# hf-upconverter.net
KiCad netlist of a schematic drawn in EAGLE
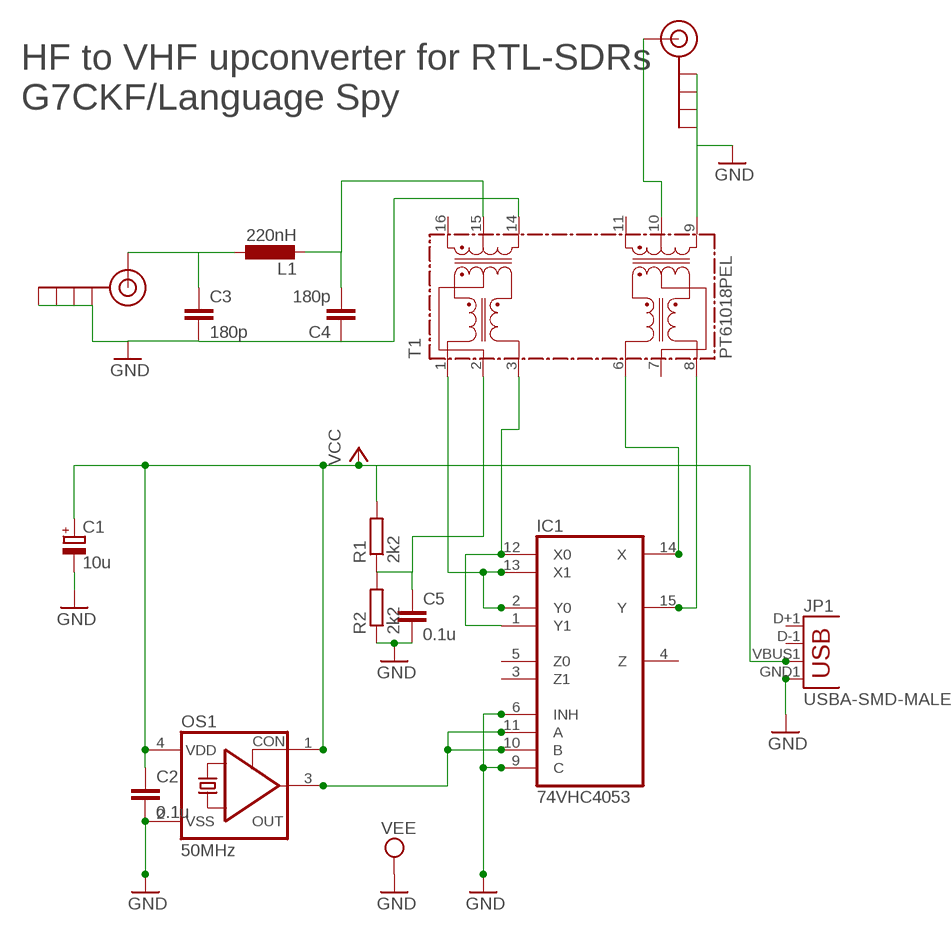
[diagram p0: schematic, sheet 1]

(export (version "E")
  (design (tool "Eeschema 10.0.6"))
  (components
    (comp (ref "C1")
      (value "10u")
      (footprint "eagle-import:PANASONIC_B")
      (libsource (lib "eagle-import") (part "CPOL-EUB"))
    )
    (comp (ref "C2")
      (value "0.1u")
      (footprint "eagle-import:C0805")
      (libsource (lib "eagle-import") (part "C-EUC0805"))
    )
    (comp (ref "C3")
      (value "180p")
      (footprint "eagle-import:C0805")
      (libsource (lib "eagle-import") (part "C-EUC0805"))
    )
    (comp (ref "C4")
      (value "180p")
      (footprint "eagle-import:C0805")
      (libsource (lib "eagle-import") (part "C-EUC0805"))
    )
    (comp (ref "C5")
      (value "0.1u")
      (footprint "eagle-import:C0805")
      (libsource (lib "eagle-import") (part "C-EUC0805"))
    )
    (comp (ref "IC1")
      (value "74VHC4053")
      (footprint "eagle-import:SO16")
      (libsource (lib "eagle-import") (part "4053D"))
    )
    (comp (ref "JP1")
      (value "USBA-SMD-MALE")
      (footprint "eagle-import:USB-A-SMT-MALE")
      (libsource (lib "eagle-import") (part "USBA-SMD-MALE"))
    )
    (comp (ref "L1")
      (value "220nH")
      (footprint "eagle-import:R1206")
      (libsource (lib "eagle-import") (part "L-EU"))
    )
    (comp (ref "OS1")
      (value "50MHz")
      (footprint "eagle-import:7.2X5.2-4-PAD")
      (libsource (lib "eagle-import") (part "OSC-OE-CFPS-32"))
    )
    (comp (ref "R1")
      (value "2k2")
      (footprint "eagle-import:R0805")
      (libsource (lib "eagle-import") (part "R-EU_R0805"))
    )
    (comp (ref "R2")
      (value "2k2")
      (footprint "eagle-import:R0805")
      (libsource (lib "eagle-import") (part "R-EU_R0805"))
    )
    (comp (ref "SMA1")
      (value "ANT")
      (footprint "eagle-import:SMA-EDGE")
      (libsource (lib "eagle-import") (part "SMA_EDGE"))
    )
    (comp (ref "SMA2")
      (value "OUT")
      (footprint "eagle-import:SMA-EDGE")
      (libsource (lib "eagle-import") (part "SMA_EDGE"))
    )
    (comp (ref "T1")
      (value "PT61018PEL")
      (footprint "eagle-import:N5")
      (libsource (lib "eagle-import") (part "TG110-E050N5"))
    )
  )
  (nets
    (net (code "1") (name "GND") (class "Default")
      (node (ref "C1") (pin "-") (pinfunction "-_-") (pintype "passive"))
      (node (ref "C2") (pin "2") (pinfunction "2_2") (pintype "passive"))
      (node (ref "C3") (pin "2") (pinfunction "2_2") (pintype "passive"))
      (node (ref "C4") (pin "1") (pinfunction "1_1") (pintype "passive"))
      (node (ref "C5") (pin "2") (pinfunction "2_2") (pintype "passive"))
      (node (ref "IC1") (pin "6") (pinfunction "INH_6") (pintype "input"))
      (node (ref "IC1") (pin "9") (pinfunction "C_9") (pintype "input"))
      (node (ref "JP1") (pin "GND1") (pinfunction "GND_GND1") (pintype "bidirectional"))
      (node (ref "OS1") (pin "2") (pinfunction "VSS_2") (pintype "power_in"))
      (node (ref "R2") (pin "1") (pinfunction "1_1") (pintype "passive"))
      (node (ref "SMA1") (pin "GND@0") (pinfunction "GND_GND@0") (pintype "bidirectional"))
      (node (ref "SMA1") (pin "GND@1") (pinfunction "GND_GND@1") (pintype "bidirectional"))
      (node (ref "SMA1") (pin "GND@2") (pinfunction "GND_GND@2") (pintype "bidirectional"))
      (node (ref "SMA1") (pin "GND@3") (pinfunction "GND_GND@3") (pintype "bidirectional"))
      (node (ref "SMA2") (pin "GND@0") (pinfunction "GND_GND@0") (pintype "bidirectional"))
      (node (ref "SMA2") (pin "GND@1") (pinfunction "GND_GND@1") (pintype "bidirectional"))
      (node (ref "SMA2") (pin "GND@2") (pinfunction "GND_GND@2") (pintype "bidirectional"))
      (node (ref "SMA2") (pin "GND@3") (pinfunction "GND_GND@3") (pintype "bidirectional"))
      (node (ref "T1") (pin "14") (pinfunction "14_14") (pintype "passive"))
      (node (ref "T1") (pin "9") (pinfunction "9_9") (pintype "passive"))
    )
    (net (code "2") (name "Net-(C4-Pad2)") (class "Default")
      (node (ref "C4") (pin "2") (pinfunction "2_2") (pintype "passive"))
      (node (ref "L1") (pin "2") (pinfunction "2_2") (pintype "passive"))
      (node (ref "T1") (pin "15") (pinfunction "15_15") (pintype "passive"))
    )
    (net (code "3") (name "Net-(C5-Pad1)") (class "Default")
      (node (ref "C5") (pin "1") (pinfunction "1_1") (pintype "passive"))
      (node (ref "R1") (pin "1") (pinfunction "1_1") (pintype "passive"))
      (node (ref "R2") (pin "2") (pinfunction "2_2") (pintype "passive"))
      (node (ref "T1") (pin "2") (pinfunction "2_2") (pintype "passive"))
    )
    (net (code "4") (name "Net-(IC1A-A)") (class "Default")
      (node (ref "IC1") (pin "10") (pinfunction "B_10") (pintype "input"))
      (node (ref "IC1") (pin "11") (pinfunction "A_11") (pintype "input"))
      (node (ref "OS1") (pin "3") (pinfunction "OUT_3") (pintype "output"))
    )
    (net (code "5") (name "Net-(IC1A-X)") (class "Default")
      (node (ref "IC1") (pin "14") (pinfunction "X_14") (pintype "bidirectional"))
      (node (ref "T1") (pin "6") (pinfunction "6_6") (pintype "passive"))
    )
    (net (code "6") (name "Net-(IC1A-X0)") (class "Default")
      (node (ref "IC1") (pin "1") (pinfunction "Y1_1") (pintype "bidirectional"))
      (node (ref "IC1") (pin "12") (pinfunction "X0_12") (pintype "bidirectional"))
      (node (ref "T1") (pin "3") (pinfunction "3_3") (pintype "passive"))
    )
    (net (code "7") (name "Net-(IC1A-X1)") (class "Default")
      (node (ref "IC1") (pin "13") (pinfunction "X1_13") (pintype "bidirectional"))
      (node (ref "IC1") (pin "2") (pinfunction "Y0_2") (pintype "bidirectional"))
      (node (ref "T1") (pin "1") (pinfunction "1_1") (pintype "passive"))
    )
    (net (code "8") (name "Net-(IC1A-Y)") (class "Default")
      (node (ref "IC1") (pin "15") (pinfunction "Y_15") (pintype "bidirectional"))
      (node (ref "T1") (pin "8") (pinfunction "8_8") (pintype "passive"))
    )
    (net (code "9") (name "Net-(SMA1-SIGNAL)") (class "Default")
      (node (ref "C3") (pin "1") (pinfunction "1_1") (pintype "passive"))
      (node (ref "L1") (pin "1") (pinfunction "1_1") (pintype "passive"))
      (node (ref "SMA1") (pin "SIG") (pinfunction "SIGNAL_SIG") (pintype "bidirectional"))
    )
    (net (code "10") (name "Net-(SMA2-SIGNAL)") (class "Default")
      (node (ref "SMA2") (pin "SIG") (pinfunction "SIGNAL_SIG") (pintype "bidirectional"))
      (node (ref "T1") (pin "10") (pinfunction "10_10") (pintype "passive"))
    )
    (net (code "11") (name "VCC") (class "Default")
      (node (ref "C1") (pin "+") (pinfunction "+_+") (pintype "passive"))
      (node (ref "C2") (pin "1") (pinfunction "1_1") (pintype "passive"))
      (node (ref "JP1") (pin "VBUS1") (pinfunction "VBUS_VBUS1") (pintype "bidirectional"))
      (node (ref "OS1") (pin "1") (pinfunction "CON_1") (pintype "input"))
      (node (ref "OS1") (pin "4") (pinfunction "VDD_4") (pintype "power_in"))
      (node (ref "R1") (pin "2") (pinfunction "2_2") (pintype "passive"))
    )
    (net (code "12") (name "unconnected-(IC1A-Z-Pad4)") (class "Default")
      (node (ref "IC1") (pin "4") (pinfunction "Z_4") (pintype "bidirectional"))
    )
    (net (code "13") (name "unconnected-(IC1A-Z0-Pad5)") (class "Default")
      (node (ref "IC1") (pin "5") (pinfunction "Z0_5") (pintype "bidirectional"))
    )
    (net (code "14") (name "unconnected-(IC1A-Z1-Pad3)") (class "Default")
      (node (ref "IC1") (pin "3") (pinfunction "Z1_3") (pintype "bidirectional"))
    )
    (net (code "15") (name "unconnected-(JP1-D+-PadD+1)") (class "Default")
      (node (ref "JP1") (pin "D+1") (pinfunction "D+_D+1") (pintype "bidirectional"))
    )
    (net (code "16") (name "unconnected-(JP1-D--PadD-1)") (class "Default")
      (node (ref "JP1") (pin "D-1") (pinfunction "D-_D-1") (pintype "bidirectional"))
    )
    (net (code "17") (name "unconnected-(T1-Pad7)") (class "Default")
      (node (ref "T1") (pin "7") (pinfunction "7_7") (pintype "passive"))
    )
    (net (code "18") (name "unconnected-(T1-Pad11)") (class "Default")
      (node (ref "T1") (pin "11") (pinfunction "11_11") (pintype "passive"))
    )
    (net (code "19") (name "unconnected-(T1-Pad16)") (class "Default")
      (node (ref "T1") (pin "16") (pinfunction "16_16") (pintype "passive"))
    )
  )
)
